# rekick2016-Flyback-v2-extra-boards.net
KiCad netlist of a schematic drawn in EAGLE
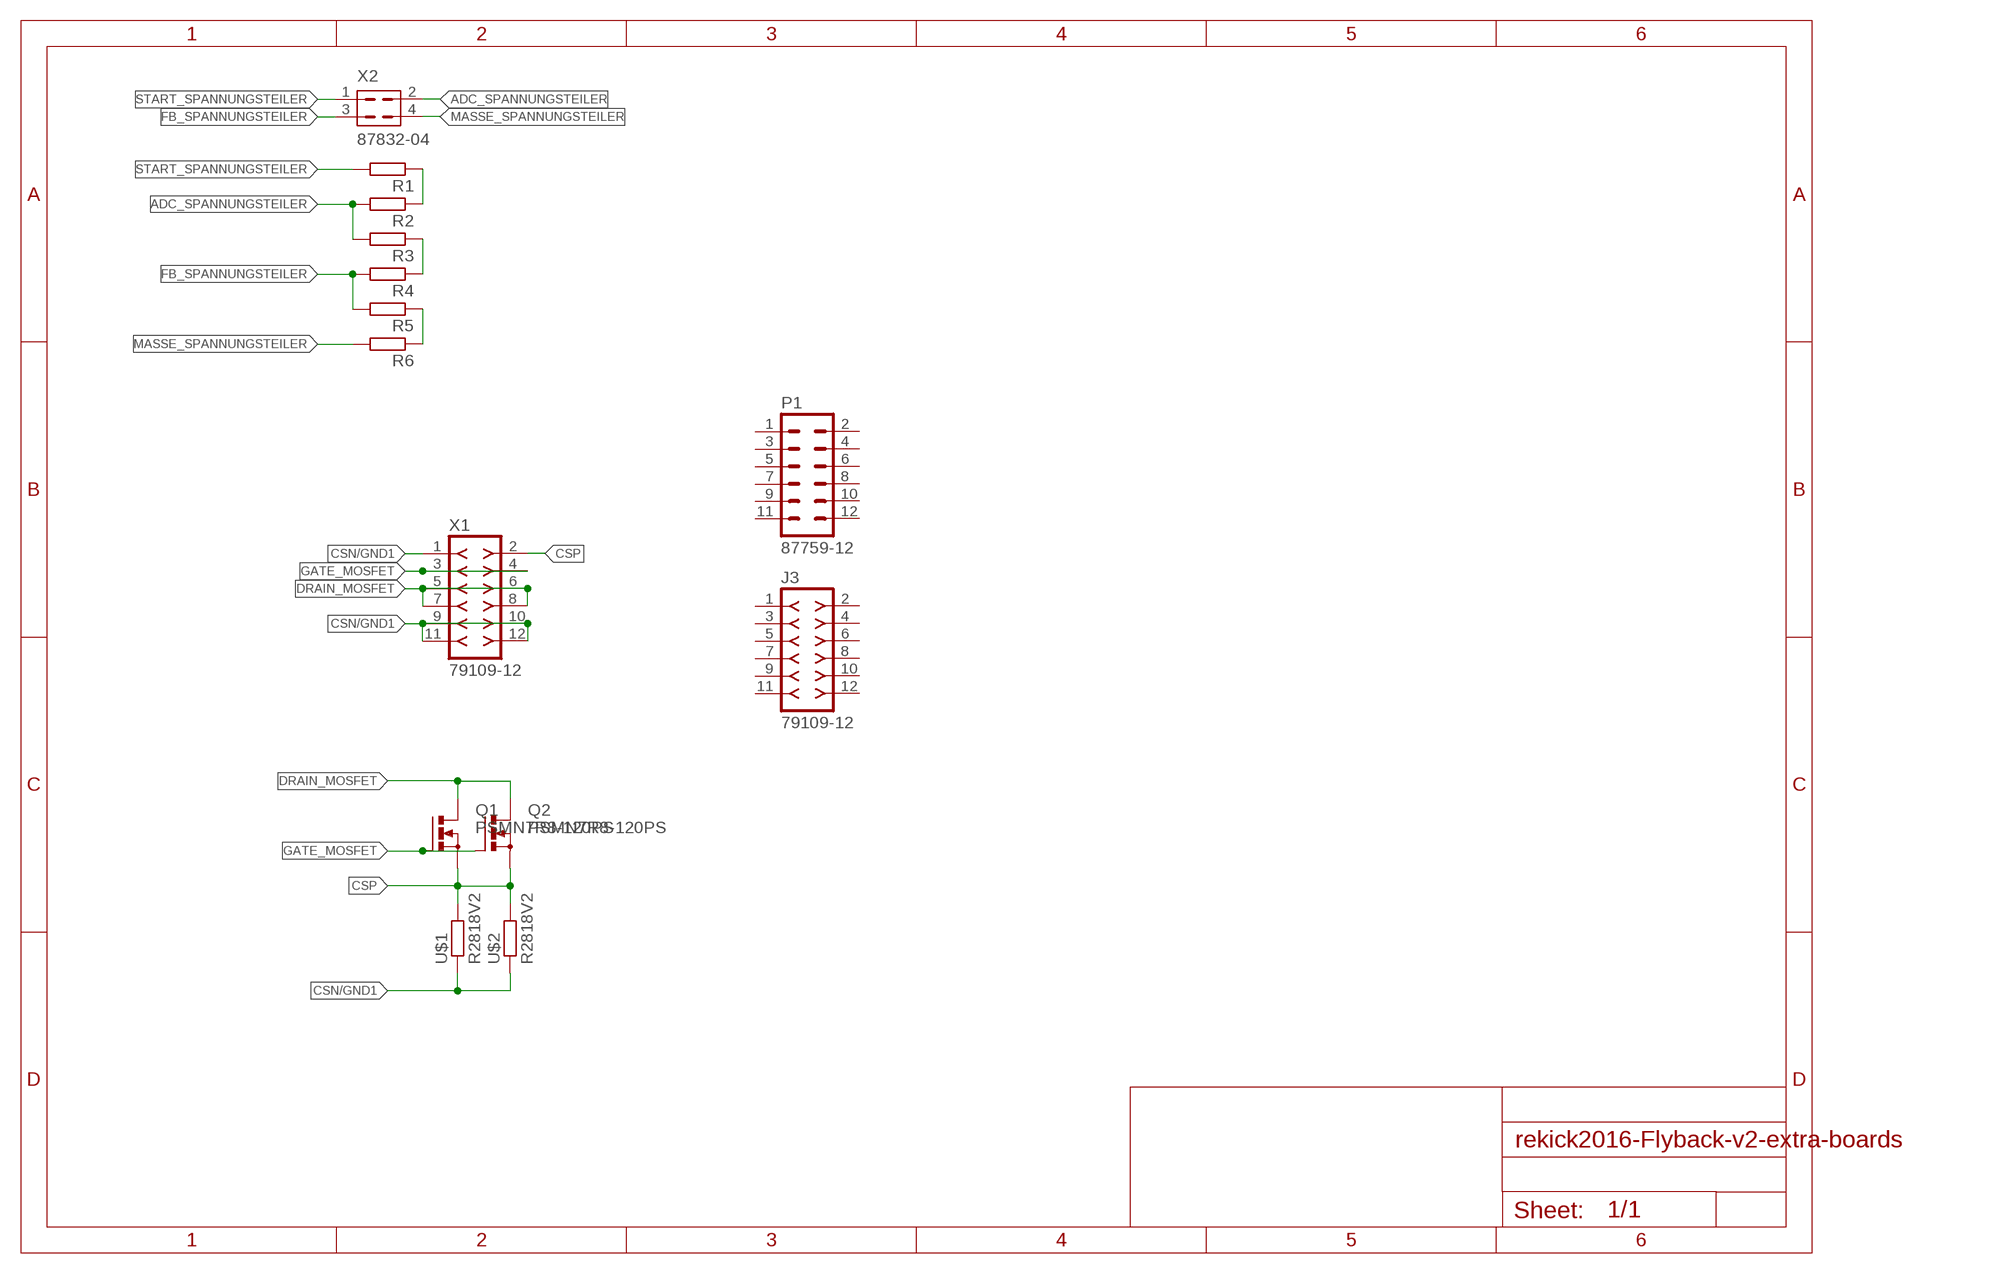
[diagram p0: schematic, sheet 1]

(export (version "E")
  (design (tool "Eeschema 10.0.6"))
  (components
    (comp (ref "J3")
      (value "79109-12")
      (footprint "eagle-import:79109-12")
      (libsource (lib "eagle-import") (part "79109-12"))
    )
    (comp (ref "P1")
      (value "87759-12")
      (footprint "eagle-import:87759-12")
      (libsource (lib "eagle-import") (part "87759-12"))
    )
    (comp (ref "Q1")
      (value "PSMN7R8-120PS")
      (footprint "eagle-import:TO220BV")
      (libsource (lib "eagle-import") (part "PMOSFET_NTO220BV"))
    )
    (comp (ref "Q2")
      (value "PSMN7R8-120PS")
      (footprint "eagle-import:TO220BV")
      (libsource (lib "eagle-import") (part "PMOSFET_NTO220BV"))
    )
    (comp (ref "R1")
      (value "R-EU_R0805")
      (footprint "eagle-import:R0805")
      (libsource (lib "eagle-import") (part "R-EU_R0805"))
    )
    (comp (ref "R2")
      (value "R-EU_R0805")
      (footprint "eagle-import:R0805")
      (libsource (lib "eagle-import") (part "R-EU_R0805"))
    )
    (comp (ref "R3")
      (value "R-EU_R0805")
      (footprint "eagle-import:R0805")
      (libsource (lib "eagle-import") (part "R-EU_R0805"))
    )
    (comp (ref "R4")
      (value "R-EU_R0805")
      (footprint "eagle-import:R0805")
      (libsource (lib "eagle-import") (part "R-EU_R0805"))
    )
    (comp (ref "R5")
      (value "R-EU_R0805")
      (footprint "eagle-import:R0805")
      (libsource (lib "eagle-import") (part "R-EU_R0805"))
    )
    (comp (ref "R6")
      (value "R-EU_R0805")
      (footprint "eagle-import:R0805")
      (libsource (lib "eagle-import") (part "R-EU_R0805"))
    )
    (comp (ref "U$1")
      (value "R2818V2")
      (footprint "eagle-import:R2818")
      (libsource (lib "eagle-import") (part "R2818V2"))
    )
    (comp (ref "U$2")
      (value "R2818V2")
      (footprint "eagle-import:R2818")
      (libsource (lib "eagle-import") (part "R2818V2"))
    )
    (comp (ref "X1")
      (value "79109-12")
      (footprint "eagle-import:79109-12")
      (libsource (lib "eagle-import") (part "79109-12"))
    )
    (comp (ref "X2")
      (value "87832-04")
      (footprint "eagle-import:87832-04")
      (libsource (lib "eagle-import") (part "87832-04"))
    )
  )
  (nets
    (net (code "1") (name "ADC_SPANNUNGSTEILER") (class "Default")
      (node (ref "R2") (pin "2") (pinfunction "2_2") (pintype "passive"))
      (node (ref "R3") (pin "2") (pinfunction "2_2") (pintype "passive"))
      (node (ref "X2") (pin "2") (pinfunction "2_2") (pintype "passive"))
    )
    (net (code "2") (name "CSN{slash}GND1") (class "Default")
      (node (ref "U$1") (pin "1") (pinfunction "1_1") (pintype "passive"))
      (node (ref "U$2") (pin "1") (pinfunction "1_1") (pintype "passive"))
      (node (ref "X1") (pin "1") (pinfunction "1_1") (pintype "passive"))
      (node (ref "X1") (pin "10") (pinfunction "10_10") (pintype "passive"))
      (node (ref "X1") (pin "11") (pinfunction "11_11") (pintype "passive"))
      (node (ref "X1") (pin "12") (pinfunction "12_12") (pintype "passive"))
      (node (ref "X1") (pin "9") (pinfunction "9_9") (pintype "passive"))
    )
    (net (code "3") (name "CSP") (class "Default")
      (node (ref "Q1") (pin "S") (pinfunction "S_S") (pintype "passive"))
      (node (ref "Q2") (pin "S") (pinfunction "S_S") (pintype "passive"))
      (node (ref "U$1") (pin "2") (pinfunction "2_2") (pintype "passive"))
      (node (ref "U$2") (pin "2") (pinfunction "2_2") (pintype "passive"))
      (node (ref "X1") (pin "2") (pinfunction "2_2") (pintype "passive"))
    )
    (net (code "4") (name "DRAIN_MOSFET") (class "Default")
      (node (ref "Q1") (pin "D") (pinfunction "D_D") (pintype "passive"))
      (node (ref "Q2") (pin "D") (pinfunction "D_D") (pintype "passive"))
      (node (ref "X1") (pin "5") (pinfunction "5_5") (pintype "passive"))
      (node (ref "X1") (pin "6") (pinfunction "6_6") (pintype "passive"))
      (node (ref "X1") (pin "7") (pinfunction "7_7") (pintype "passive"))
      (node (ref "X1") (pin "8") (pinfunction "8_8") (pintype "passive"))
    )
    (net (code "5") (name "FB_SPANNUNGSTEILER") (class "Default")
      (node (ref "R4") (pin "2") (pinfunction "2_2") (pintype "passive"))
      (node (ref "R5") (pin "2") (pinfunction "2_2") (pintype "passive"))
      (node (ref "X2") (pin "3") (pinfunction "3_3") (pintype "passive"))
    )
    (net (code "6") (name "GATE_MOSFET") (class "Default")
      (node (ref "Q1") (pin "G") (pinfunction "G_G") (pintype "passive"))
      (node (ref "Q2") (pin "G") (pinfunction "G_G") (pintype "passive"))
      (node (ref "X1") (pin "3") (pinfunction "3_3") (pintype "passive"))
      (node (ref "X1") (pin "4") (pinfunction "4_4") (pintype "passive"))
    )
    (net (code "7") (name "MASSE_SPANNUNGSTEILER") (class "Default")
      (node (ref "R6") (pin "2") (pinfunction "2_2") (pintype "passive"))
      (node (ref "X2") (pin "4") (pinfunction "4_4") (pintype "passive"))
    )
    (net (code "8") (name "Net-(R1-Pad1)") (class "Default")
      (node (ref "R1") (pin "1") (pinfunction "1_1") (pintype "passive"))
      (node (ref "R2") (pin "1") (pinfunction "1_1") (pintype "passive"))
    )
    (net (code "9") (name "Net-(R3-Pad1)") (class "Default")
      (node (ref "R3") (pin "1") (pinfunction "1_1") (pintype "passive"))
      (node (ref "R4") (pin "1") (pinfunction "1_1") (pintype "passive"))
    )
    (net (code "10") (name "Net-(R5-Pad1)") (class "Default")
      (node (ref "R5") (pin "1") (pinfunction "1_1") (pintype "passive"))
      (node (ref "R6") (pin "1") (pinfunction "1_1") (pintype "passive"))
    )
    (net (code "11") (name "START_SPANNUNGSTEILER") (class "Default")
      (node (ref "R1") (pin "2") (pinfunction "2_2") (pintype "passive"))
      (node (ref "X2") (pin "1") (pinfunction "1_1") (pintype "passive"))
    )
    (net (code "12") (name "unconnected-(J3-Pad1)") (class "Default")
      (node (ref "J3") (pin "1") (pinfunction "1_1") (pintype "passive"))
    )
    (net (code "13") (name "unconnected-(J3-Pad2)") (class "Default")
      (node (ref "J3") (pin "2") (pinfunction "2_2") (pintype "passive"))
    )
    (net (code "14") (name "unconnected-(J3-Pad3)") (class "Default")
      (node (ref "J3") (pin "3") (pinfunction "3_3") (pintype "passive"))
    )
    (net (code "15") (name "unconnected-(J3-Pad4)") (class "Default")
      (node (ref "J3") (pin "4") (pinfunction "4_4") (pintype "passive"))
    )
    (net (code "16") (name "unconnected-(J3-Pad5)") (class "Default")
      (node (ref "J3") (pin "5") (pinfunction "5_5") (pintype "passive"))
    )
    (net (code "17") (name "unconnected-(J3-Pad6)") (class "Default")
      (node (ref "J3") (pin "6") (pinfunction "6_6") (pintype "passive"))
    )
    (net (code "18") (name "unconnected-(J3-Pad7)") (class "Default")
      (node (ref "J3") (pin "7") (pinfunction "7_7") (pintype "passive"))
    )
    (net (code "19") (name "unconnected-(J3-Pad8)") (class "Default")
      (node (ref "J3") (pin "8") (pinfunction "8_8") (pintype "passive"))
    )
    (net (code "20") (name "unconnected-(J3-Pad9)") (class "Default")
      (node (ref "J3") (pin "9") (pinfunction "9_9") (pintype "passive"))
    )
    (net (code "21") (name "unconnected-(J3-Pad10)") (class "Default")
      (node (ref "J3") (pin "10") (pinfunction "10_10") (pintype "passive"))
    )
    (net (code "22") (name "unconnected-(J3-Pad11)") (class "Default")
      (node (ref "J3") (pin "11") (pinfunction "11_11") (pintype "passive"))
    )
    (net (code "23") (name "unconnected-(J3-Pad12)") (class "Default")
      (node (ref "J3") (pin "12") (pinfunction "12_12") (pintype "passive"))
    )
    (net (code "24") (name "unconnected-(P1-Pad1)") (class "Default")
      (node (ref "P1") (pin "1") (pinfunction "1_1") (pintype "passive"))
    )
    (net (code "25") (name "unconnected-(P1-Pad2)") (class "Default")
      (node (ref "P1") (pin "2") (pinfunction "2_2") (pintype "passive"))
    )
    (net (code "26") (name "unconnected-(P1-Pad3)") (class "Default")
      (node (ref "P1") (pin "3") (pinfunction "3_3") (pintype "passive"))
    )
    (net (code "27") (name "unconnected-(P1-Pad4)") (class "Default")
      (node (ref "P1") (pin "4") (pinfunction "4_4") (pintype "passive"))
    )
    (net (code "28") (name "unconnected-(P1-Pad5)") (class "Default")
      (node (ref "P1") (pin "5") (pinfunction "5_5") (pintype "passive"))
    )
    (net (code "29") (name "unconnected-(P1-Pad6)") (class "Default")
      (node (ref "P1") (pin "6") (pinfunction "6_6") (pintype "passive"))
    )
    (net (code "30") (name "unconnected-(P1-Pad7)") (class "Default")
      (node (ref "P1") (pin "7") (pinfunction "7_7") (pintype "passive"))
    )
    (net (code "31") (name "unconnected-(P1-Pad8)") (class "Default")
      (node (ref "P1") (pin "8") (pinfunction "8_8") (pintype "passive"))
    )
    (net (code "32") (name "unconnected-(P1-Pad9)") (class "Default")
      (node (ref "P1") (pin "9") (pinfunction "9_9") (pintype "passive"))
    )
    (net (code "33") (name "unconnected-(P1-Pad10)") (class "Default")
      (node (ref "P1") (pin "10") (pinfunction "10_10") (pintype "passive"))
    )
    (net (code "34") (name "unconnected-(P1-Pad11)") (class "Default")
      (node (ref "P1") (pin "11") (pinfunction "11_11") (pintype "passive"))
    )
    (net (code "35") (name "unconnected-(P1-Pad12)") (class "Default")
      (node (ref "P1") (pin "12") (pinfunction "12_12") (pintype "passive"))
    )
  )
)
